# IFE_PDB_2019.net
KiCad netlist of a schematic drawn in Altium Designer
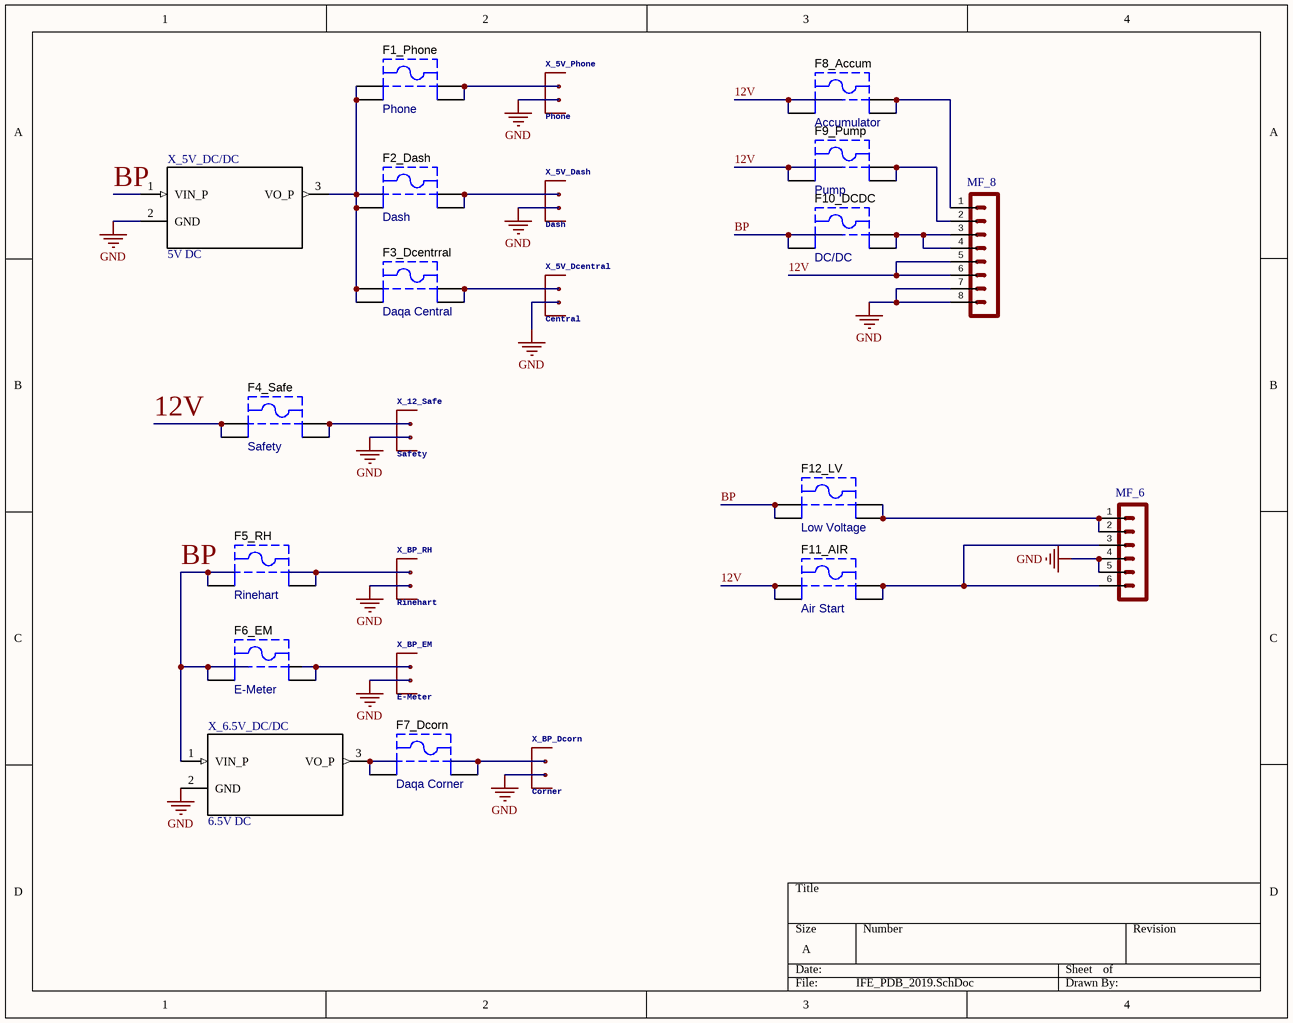
[diagram p0: IFE_PDB_2019.SchDoc]

(export (version "E")
  (design (tool "Eeschema 10.0.6"))
  (components
    (comp (ref "F1_Phone")
      (value "Phone")
      (footprint "KSTN-3568_V")
      (description "Fuse Holder, 20 A, 500 V, -50 to 145 degC, 4-Pin THD, RoHS")
      (fields (field (name "MANUFACTURER") "Keystone"))
      (libsource (lib "Altium Content Vault") (part "FUSE_HOLDER-4"))
    )
    (comp (ref "F2_Dash")
      (value "Dash")
      (footprint "KSTN-3568_V")
      (description "Fuse Holder, 20 A, 500 V, -50 to 145 degC, 4-Pin THD, RoHS")
      (fields (field (name "MANUFACTURER") "Keystone"))
      (libsource (lib "Altium Content Vault") (part "FUSE_HOLDER-4"))
    )
    (comp (ref "F3_Dcentrral")
      (value "Daqa Central")
      (footprint "KSTN-3568_V")
      (description "Fuse Holder, 20 A, 500 V, -50 to 145 degC, 4-Pin THD, RoHS")
      (fields (field (name "MANUFACTURER") "Keystone"))
      (libsource (lib "Altium Content Vault") (part "FUSE_HOLDER-4"))
    )
    (comp (ref "F4_Safe")
      (value "Safety")
      (footprint "KSTN-3568_V")
      (description "Fuse Holder, 20 A, 500 V, -50 to 145 degC, 4-Pin THD, RoHS")
      (fields (field (name "MANUFACTURER") "Keystone"))
      (libsource (lib "Altium Content Vault") (part "FUSE_HOLDER-4"))
    )
    (comp (ref "F5_RH")
      (value "Rinehart")
      (footprint "KSTN-3568_V")
      (description "Fuse Holder, 20 A, 500 V, -50 to 145 degC, 4-Pin THD, RoHS")
      (fields (field (name "MANUFACTURER") "Keystone"))
      (libsource (lib "Altium Content Vault") (part "FUSE_HOLDER-4"))
    )
    (comp (ref "F6_EM")
      (value "E-Meter")
      (footprint "KSTN-3568_V")
      (description "Fuse Holder, 20 A, 500 V, -50 to 145 degC, 4-Pin THD, RoHS")
      (fields (field (name "MANUFACTURER") "Keystone"))
      (libsource (lib "Altium Content Vault") (part "FUSE_HOLDER-4"))
    )
    (comp (ref "F7_Dcorn")
      (value "Daqa Corner")
      (footprint "KSTN-3568_V")
      (description "Fuse Holder, 20 A, 500 V, -50 to 145 degC, 4-Pin THD, RoHS")
      (fields (field (name "MANUFACTURER") "Keystone"))
      (libsource (lib "Altium Content Vault") (part "FUSE_HOLDER-4"))
    )
    (comp (ref "F8_Accum")
      (value "Accumulator")
      (footprint "KSTN-3568_V")
      (description "Fuse Holder, 20 A, 500 V, -50 to 145 degC, 4-Pin THD, RoHS")
      (fields (field (name "MANUFACTURER") "Keystone"))
      (libsource (lib "Altium Content Vault") (part "FUSE_HOLDER-4"))
    )
    (comp (ref "F9_Pump")
      (value "Pump")
      (footprint "KSTN-3568_V")
      (description "Fuse Holder, 20 A, 500 V, -50 to 145 degC, 4-Pin THD, RoHS")
      (fields (field (name "MANUFACTURER") "Keystone"))
      (libsource (lib "Altium Content Vault") (part "FUSE_HOLDER-4"))
    )
    (comp (ref "F10_DCDC")
      (value "DC/DC")
      (footprint "KSTN-3568_V")
      (description "Fuse Holder, 20 A, 500 V, -50 to 145 degC, 4-Pin THD, RoHS")
      (fields (field (name "MANUFACTURER") "Keystone"))
      (libsource (lib "Altium Content Vault") (part "FUSE_HOLDER-4"))
    )
    (comp (ref "F11_AIR")
      (value "Air Start")
      (footprint "KSTN-3568_V")
      (description "Fuse Holder, 20 A, 500 V, -50 to 145 degC, 4-Pin THD, RoHS")
      (fields (field (name "MANUFACTURER") "Keystone"))
      (libsource (lib "Altium Content Vault") (part "FUSE_HOLDER-4"))
    )
    (comp (ref "F12_LV")
      (value "Low Voltage")
      (footprint "KSTN-3568_V")
      (description "Fuse Holder, 20 A, 500 V, -50 to 145 degC, 4-Pin THD, RoHS")
      (fields (field (name "MANUFACTURER") "Keystone"))
      (libsource (lib "Altium Content Vault") (part "FUSE_HOLDER-4"))
    )
    (comp (ref "MF_6")
      (value "~")
      (footprint "172065-0306")
      (fields (field (name "MANUFACTURER") "Molex") (field (name "MANUFACTURER PART NUMBER") "172065-0306"))
      (libsource (lib "ife19_Elec_Conn_Library") (part "POS6_MgF172065-0306"))
    )
    (comp (ref "MF_8")
      (value "~")
      (footprint "172065-0308")
      (description "Conn Power HDR 8 POS 5.7mm Solder ST Thru-Hole 8 Terminal 1 Port Mega-Fit® Frame")
      (fields (field (name "MANUFACTURER") "Molex") (field (name "MANUFACTURER PART NUMBER") "172065-0308"))
      (libsource (lib "ife19_Elec_Conn_Library") (part "POS8_MgF172065-0308"))
    )
    (comp (ref "X_5V_Dash")
      (value "Dash")
      (footprint "505575-02")
      (description "Molex 505575-02 2 Position 2.00mm pitch connector wire to board connector Datasheet")
      (fields (field (name "LIBRARYNAME") "MOLEX Micro-Lock"))
      (libsource (lib "MOLEX Micro-Lock") (part "505575-02"))
    )
    (comp (ref "X_5V_DC/DC")
      (value "5V DC")
      (footprint "*CONV_V7805-2000")
      (description "V78-2000 Series 13 W Single Output 12V Straight Non Isolated Switching Regulator")
      (fields (field (name "MP") "V7805-2000") (field (name "DIGI-KEY_PART_NUMBER") "102-2175-ND"))
      (libsource (lib "V7805-2000") (part "V7805-2000"))
    )
    (comp (ref "X_5V_Dcentral")
      (value "Central")
      (footprint "505575-02")
      (description "Molex 505575-02 2 Position 2.00mm pitch connector wire to board connector Datasheet")
      (fields (field (name "LIBRARYNAME") "MOLEX Micro-Lock"))
      (libsource (lib "MOLEX Micro-Lock") (part "505575-02"))
    )
    (comp (ref "X_5V_Phone")
      (value "Phone")
      (footprint "505575-02")
      (fields (field (name "LIBRARYNAME") "MOLEX Micro-Lock"))
      (libsource (lib "MOLEX Micro-Lock") (part "505575-02"))
    )
    (comp (ref "X_6.5V_DC/DC")
      (value "6.5V DC")
      (footprint "*CONV_V7805-2000")
      (description "Male Header, Pitch 2.54 mm, 1 x 3 Position, Height 8.38 mm, Tail Length 3.18 mm, RoHS, Bulk")
      (fields (field (name "MP") "V7805-2000") (field (name "DIGI-KEY_PART_NUMBER") "102-2175-ND"))
      (libsource (lib "V7805-2000") (part "V7805-2000"))
    )
    (comp (ref "X_12_Safe")
      (value "Safety")
      (footprint "505575-02")
      (description "Molex 505575-02 2 Position 2.00mm pitch connector wire to board connector Datasheet")
      (fields (field (name "LIBRARYNAME") "MOLEX Micro-Lock"))
      (libsource (lib "MOLEX Micro-Lock") (part "505575-02"))
    )
    (comp (ref "X_BP_Dcorn")
      (value "Corner")
      (footprint "505575-02")
      (description "Molex 505575-02 2 Position 2.00mm pitch connector wire to board connector Datasheet")
      (fields (field (name "LIBRARYNAME") "MOLEX Micro-Lock"))
      (libsource (lib "MOLEX Micro-Lock") (part "505575-02"))
    )
    (comp (ref "X_BP_EM")
      (value "E-Meter")
      (footprint "505575-02")
      (description "Molex 505575-02 2 Position 2.00mm pitch connector wire to board connector Datasheet")
      (fields (field (name "LIBRARYNAME") "MOLEX Micro-Lock"))
      (libsource (lib "MOLEX Micro-Lock") (part "505575-02"))
    )
    (comp (ref "X_BP_RH")
      (value "Rinehart")
      (footprint "505575-02")
      (description "Molex 505575-02 2 Position 2.00mm pitch connector wire to board connector Datasheet")
      (fields (field (name "LIBRARYNAME") "MOLEX Micro-Lock"))
      (libsource (lib "MOLEX Micro-Lock") (part "505575-02"))
    )
  )
  (nets
    (net (code "1") (name "/12V") (class "Default")
      (node (ref "F11_AIR") (pin "1") (pinfunction "1_1") (pintype "passive"))
      (node (ref "F11_AIR") (pin "2") (pinfunction "2_2") (pintype "passive"))
      (node (ref "F4_Safe") (pin "1") (pinfunction "1_1") (pintype "passive"))
      (node (ref "F4_Safe") (pin "2") (pinfunction "2_2") (pintype "passive"))
      (node (ref "F8_Accum") (pin "1") (pinfunction "1_1") (pintype "passive"))
      (node (ref "F8_Accum") (pin "2") (pinfunction "2_2") (pintype "passive"))
      (node (ref "F9_Pump") (pin "1") (pinfunction "1_1") (pintype "passive"))
      (node (ref "F9_Pump") (pin "2") (pinfunction "2_2") (pintype "passive"))
      (node (ref "MF_8") (pin "5") (pinfunction "5_5") (pintype "passive"))
      (node (ref "MF_8") (pin "6") (pinfunction "6_6") (pintype "passive"))
    )
    (net (code "2") (name "/BP") (class "Default")
      (node (ref "F10_DCDC") (pin "1") (pinfunction "1_1") (pintype "passive"))
      (node (ref "F10_DCDC") (pin "2") (pinfunction "2_2") (pintype "passive"))
      (node (ref "F12_LV") (pin "1") (pinfunction "1_1") (pintype "passive"))
      (node (ref "F12_LV") (pin "2") (pinfunction "2_2") (pintype "passive"))
      (node (ref "F5_RH") (pin "1") (pinfunction "1_1") (pintype "passive"))
      (node (ref "F5_RH") (pin "2") (pinfunction "2_2") (pintype "passive"))
      (node (ref "F6_EM") (pin "1") (pinfunction "1_1") (pintype "passive"))
      (node (ref "F6_EM") (pin "2") (pinfunction "2_2") (pintype "passive"))
      (node (ref "X_5V_DC/DC") (pin "1") (pinfunction "VIN_P_1") (pintype "input"))
      (node (ref "X_6.5V_DC/DC") (pin "1") (pinfunction "VIN_P_1") (pintype "input"))
    )
    (net (code "3") (name "GND") (class "Default")
      (node (ref "MF_6") (pin "4") (pinfunction "4_4") (pintype "passive"))
      (node (ref "MF_6") (pin "5") (pinfunction "5_5") (pintype "passive"))
      (node (ref "MF_8") (pin "7") (pinfunction "7_7") (pintype "passive"))
      (node (ref "MF_8") (pin "8") (pinfunction "8_8") (pintype "passive"))
      (node (ref "X_12_Safe") (pin "2") (pinfunction "2_2") (pintype "passive"))
      (node (ref "X_5V_DC/DC") (pin "2") (pinfunction "GND_2") (pintype "power_in"))
      (node (ref "X_5V_Dash") (pin "2") (pinfunction "2_2") (pintype "passive"))
      (node (ref "X_5V_Dcentral") (pin "2") (pinfunction "2_2") (pintype "passive"))
      (node (ref "X_5V_Phone") (pin "2") (pinfunction "2_2") (pintype "passive"))
      (node (ref "X_6.5V_DC/DC") (pin "2") (pinfunction "GND_2") (pintype "power_in"))
      (node (ref "X_BP_Dcorn") (pin "2") (pinfunction "2_2") (pintype "passive"))
      (node (ref "X_BP_EM") (pin "2") (pinfunction "2_2") (pintype "passive"))
      (node (ref "X_BP_RH") (pin "2") (pinfunction "2_2") (pintype "passive"))
    )
    (net (code "4") (name "Net-(F1_Phone-Pad3)") (class "Default")
      (node (ref "F1_Phone") (pin "3") (pinfunction "3_3") (pintype "passive"))
      (node (ref "F1_Phone") (pin "4") (pinfunction "4_4") (pintype "passive"))
      (node (ref "X_5V_Phone") (pin "1") (pinfunction "1_1") (pintype "passive"))
    )
    (net (code "5") (name "Net-(F2_Dash-Pad3)") (class "Default")
      (node (ref "F2_Dash") (pin "3") (pinfunction "3_3") (pintype "passive"))
      (node (ref "F2_Dash") (pin "4") (pinfunction "4_4") (pintype "passive"))
      (node (ref "X_5V_Dash") (pin "1") (pinfunction "1_1") (pintype "passive"))
    )
    (net (code "6") (name "Net-(F3_Dcentrral-Pad3)") (class "Default")
      (node (ref "F3_Dcentrral") (pin "3") (pinfunction "3_3") (pintype "passive"))
      (node (ref "F3_Dcentrral") (pin "4") (pinfunction "4_4") (pintype "passive"))
      (node (ref "X_5V_Dcentral") (pin "1") (pinfunction "1_1") (pintype "passive"))
    )
    (net (code "7") (name "Net-(F4_Safe-Pad3)") (class "Default")
      (node (ref "F4_Safe") (pin "3") (pinfunction "3_3") (pintype "passive"))
      (node (ref "F4_Safe") (pin "4") (pinfunction "4_4") (pintype "passive"))
      (node (ref "X_12_Safe") (pin "1") (pinfunction "1_1") (pintype "passive"))
    )
    (net (code "8") (name "Net-(F5_RH-Pad3)") (class "Default")
      (node (ref "F5_RH") (pin "3") (pinfunction "3_3") (pintype "passive"))
      (node (ref "F5_RH") (pin "4") (pinfunction "4_4") (pintype "passive"))
      (node (ref "X_BP_RH") (pin "1") (pinfunction "1_1") (pintype "passive"))
    )
    (net (code "9") (name "Net-(F6_EM-Pad3)") (class "Default")
      (node (ref "F6_EM") (pin "3") (pinfunction "3_3") (pintype "passive"))
      (node (ref "F6_EM") (pin "4") (pinfunction "4_4") (pintype "passive"))
      (node (ref "X_BP_EM") (pin "1") (pinfunction "1_1") (pintype "passive"))
    )
    (net (code "10") (name "Net-(F7_Dcorn-Pad3)") (class "Default")
      (node (ref "F7_Dcorn") (pin "3") (pinfunction "3_3") (pintype "passive"))
      (node (ref "F7_Dcorn") (pin "4") (pinfunction "4_4") (pintype "passive"))
      (node (ref "X_BP_Dcorn") (pin "1") (pinfunction "1_1") (pintype "passive"))
    )
    (net (code "11") (name "Net-(F8_Accum-Pad3)") (class "Default")
      (node (ref "F8_Accum") (pin "3") (pinfunction "3_3") (pintype "passive"))
      (node (ref "F8_Accum") (pin "4") (pinfunction "4_4") (pintype "passive"))
      (node (ref "MF_8") (pin "1") (pinfunction "1_1") (pintype "passive"))
    )
    (net (code "12") (name "Net-(F9_Pump-Pad3)") (class "Default")
      (node (ref "F9_Pump") (pin "3") (pinfunction "3_3") (pintype "passive"))
      (node (ref "F9_Pump") (pin "4") (pinfunction "4_4") (pintype "passive"))
      (node (ref "MF_8") (pin "2") (pinfunction "2_2") (pintype "passive"))
    )
    (net (code "13") (name "Net-(F10_DCDC-Pad3)") (class "Default")
      (node (ref "F10_DCDC") (pin "3") (pinfunction "3_3") (pintype "passive"))
      (node (ref "F10_DCDC") (pin "4") (pinfunction "4_4") (pintype "passive"))
      (node (ref "MF_8") (pin "3") (pinfunction "3_3") (pintype "passive"))
      (node (ref "MF_8") (pin "4") (pinfunction "4_4") (pintype "passive"))
    )
    (net (code "14") (name "Net-(F11_AIR-Pad3)") (class "Default")
      (node (ref "F11_AIR") (pin "3") (pinfunction "3_3") (pintype "passive"))
      (node (ref "F11_AIR") (pin "4") (pinfunction "4_4") (pintype "passive"))
      (node (ref "MF_6") (pin "3") (pinfunction "3_3") (pintype "passive"))
      (node (ref "MF_6") (pin "6") (pinfunction "6_6") (pintype "passive"))
    )
    (net (code "15") (name "Net-(F12_LV-Pad3)") (class "Default")
      (node (ref "F12_LV") (pin "3") (pinfunction "3_3") (pintype "passive"))
      (node (ref "F12_LV") (pin "4") (pinfunction "4_4") (pintype "passive"))
      (node (ref "MF_6") (pin "1") (pinfunction "1_1") (pintype "passive"))
      (node (ref "MF_6") (pin "2") (pinfunction "2_2") (pintype "passive"))
    )
    (net (code "16") (name "Net-(X_5V_DC/DC-VO_P)") (class "Default")
      (node (ref "F1_Phone") (pin "1") (pinfunction "1_1") (pintype "passive"))
      (node (ref "F1_Phone") (pin "2") (pinfunction "2_2") (pintype "passive"))
      (node (ref "F2_Dash") (pin "1") (pinfunction "1_1") (pintype "passive"))
      (node (ref "F2_Dash") (pin "2") (pinfunction "2_2") (pintype "passive"))
      (node (ref "F3_Dcentrral") (pin "1") (pinfunction "1_1") (pintype "passive"))
      (node (ref "F3_Dcentrral") (pin "2") (pinfunction "2_2") (pintype "passive"))
      (node (ref "X_5V_DC/DC") (pin "3") (pinfunction "VO_P_3") (pintype "output"))
    )
    (net (code "17") (name "Net-(X_6.5V_DC/DC-VO_P)") (class "Default")
      (node (ref "F7_Dcorn") (pin "1") (pinfunction "1_1") (pintype "passive"))
      (node (ref "F7_Dcorn") (pin "2") (pinfunction "2_2") (pintype "passive"))
      (node (ref "X_6.5V_DC/DC") (pin "3") (pinfunction "VO_P_3") (pintype "output"))
    )
  )
)
